# Display_Interfaces.net
KiCad netlist of a schematic drawn in Altium Designer
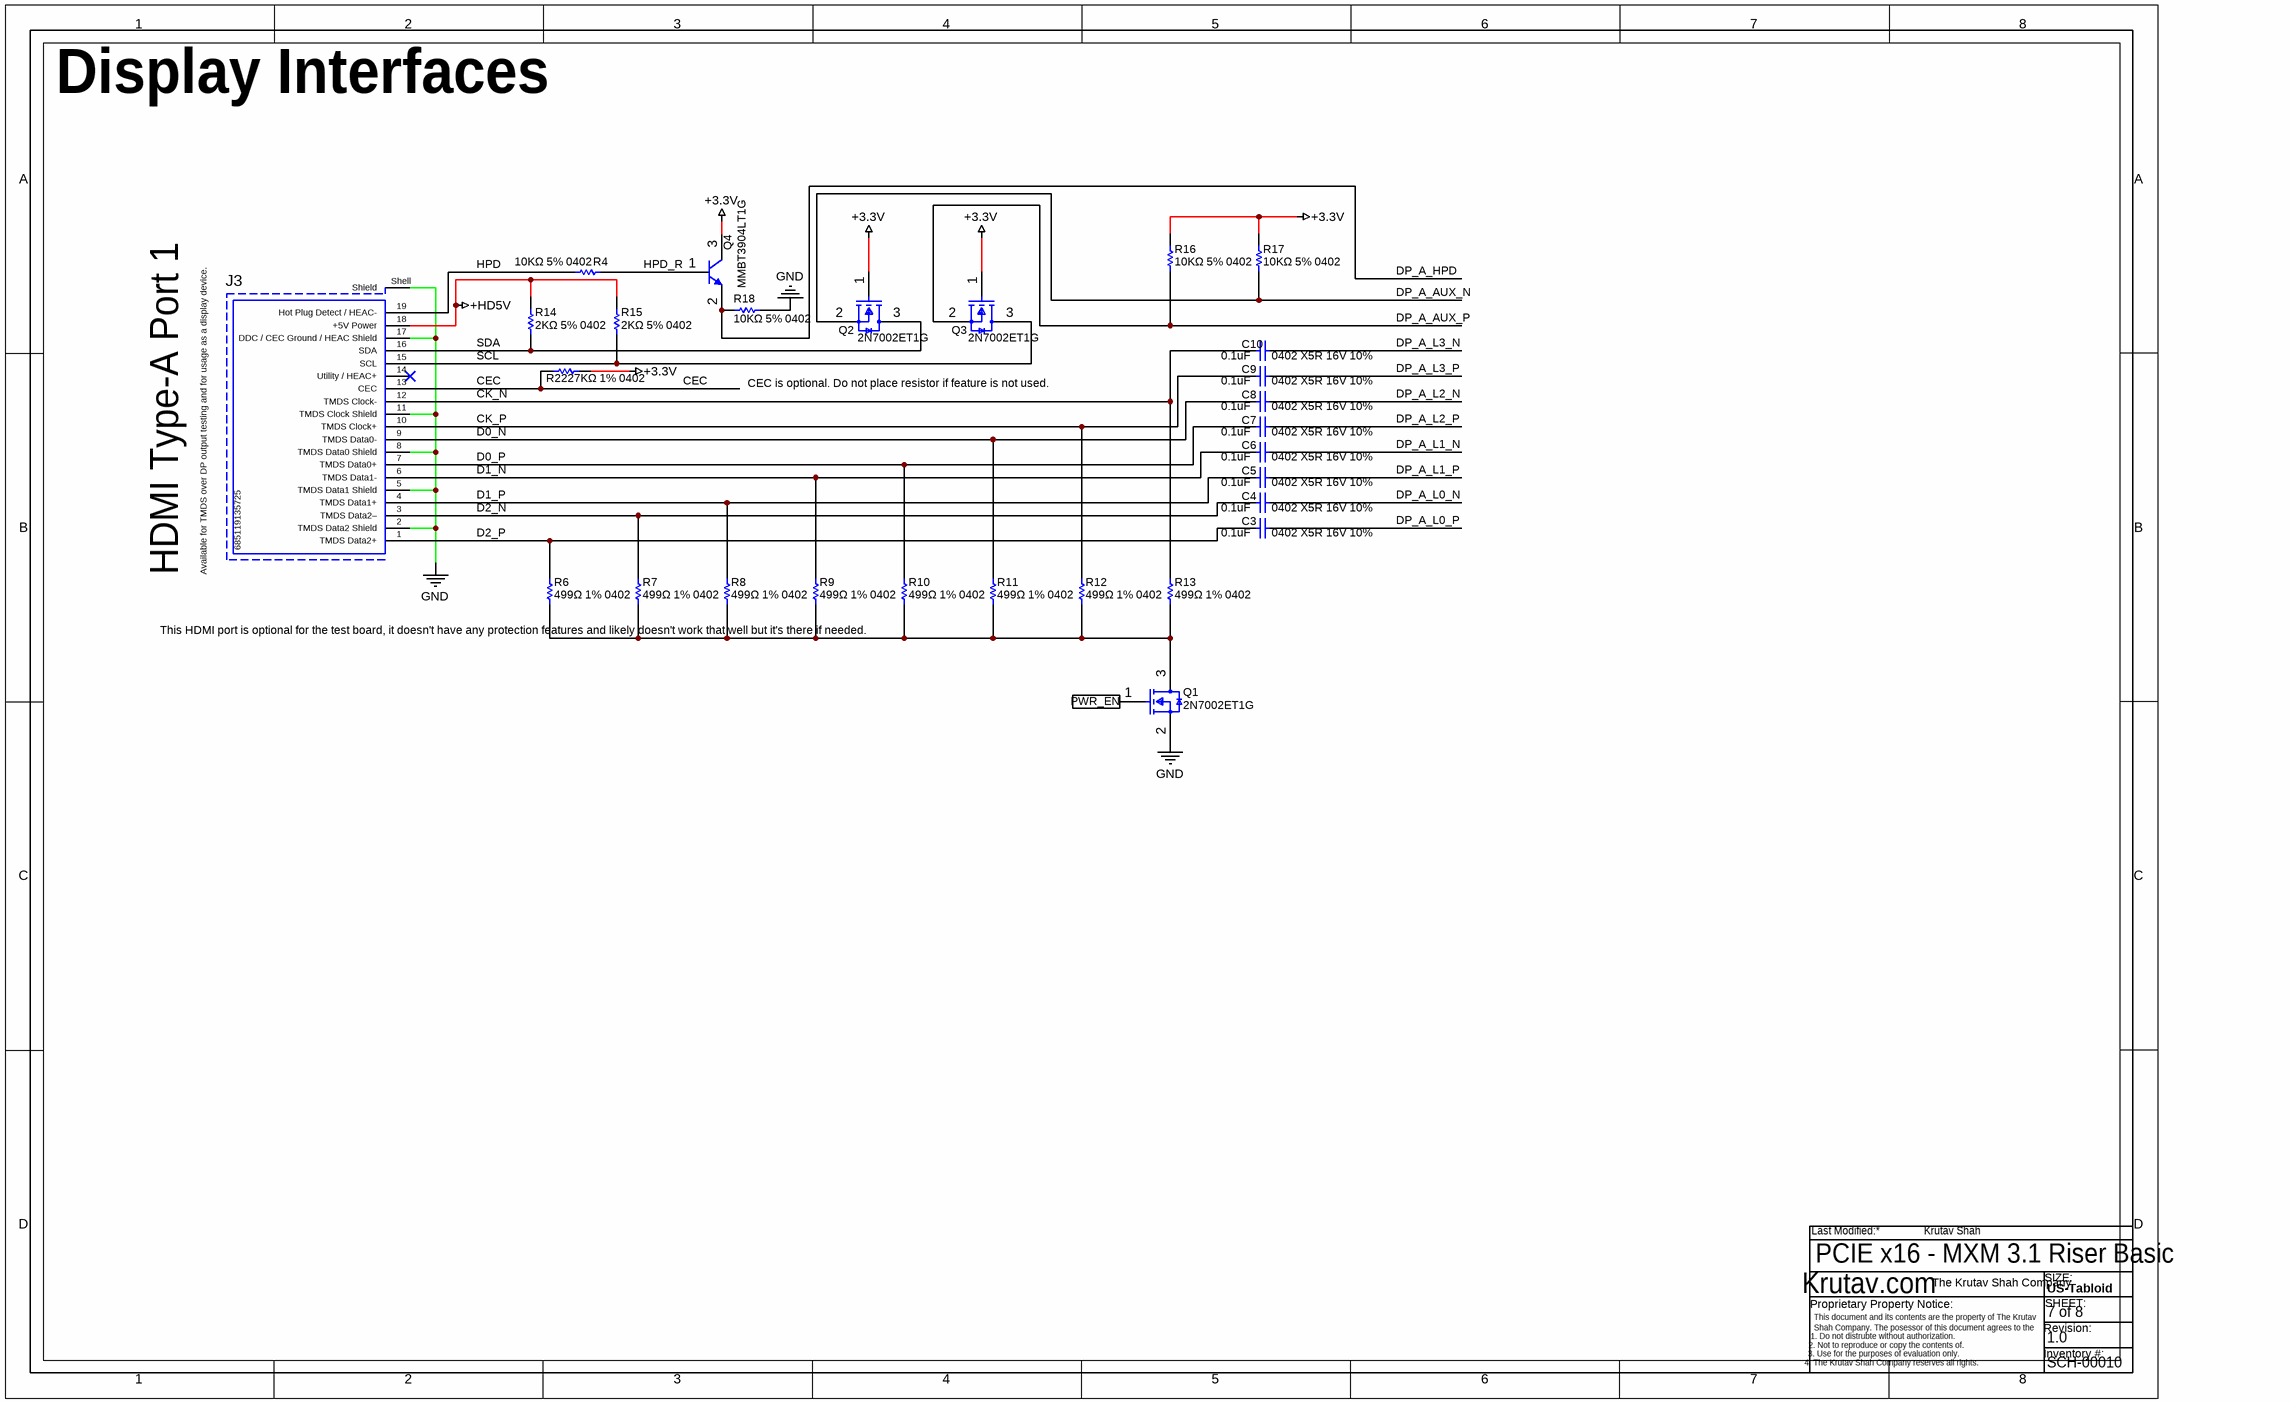
[diagram p0: Display Interfaces.SchDoc]

(export (version "E")
  (design (tool "Eeschema 10.0.6"))
  (components
    (comp (ref "C3")
      (value "0.1uF       0402 X5R 16V 10%")
      (footprint "CAPC0603X33X15NL03T05")
      (fields (field (name "MANUFACTURER") "Samsung") (field (name "PART NUMBER") "CL03A224MQ3NNNC"))
      (libsource (lib "Altium Content Vault") (part "CAP"))
    )
    (comp (ref "C4")
      (value "0.1uF       0402 X5R 16V 10%")
      (footprint "CAPC0603X33X15NL03T05")
      (fields (field (name "MANUFACTURER") "Samsung") (field (name "PART NUMBER") "CL03A224MQ3NNNC"))
      (libsource (lib "Altium Content Vault") (part "CAP"))
    )
    (comp (ref "C5")
      (value "0.1uF       0402 X5R 16V 10%")
      (footprint "CAPC0603X33X15NL03T05")
      (fields (field (name "MANUFACTURER") "Samsung") (field (name "PART NUMBER") "CL03A224MQ3NNNC"))
      (libsource (lib "Altium Content Vault") (part "CAP"))
    )
    (comp (ref "C6")
      (value "0.1uF       0402 X5R 16V 10%")
      (footprint "CAPC0603X33X15NL03T05")
      (fields (field (name "MANUFACTURER") "Samsung") (field (name "PART NUMBER") "CL03A224MQ3NNNC"))
      (libsource (lib "Altium Content Vault") (part "CAP"))
    )
    (comp (ref "C7")
      (value "0.1uF       0402 X5R 16V 10%")
      (footprint "CAPC0603X33X15NL03T05")
      (fields (field (name "MANUFACTURER") "Samsung") (field (name "PART NUMBER") "CL03A224MQ3NNNC"))
      (libsource (lib "Altium Content Vault") (part "CAP"))
    )
    (comp (ref "C8")
      (value "0.1uF       0402 X5R 16V 10%")
      (footprint "CAPC0603X33X15NL03T05")
      (fields (field (name "MANUFACTURER") "Samsung") (field (name "PART NUMBER") "CL03A224MQ3NNNC"))
      (libsource (lib "Altium Content Vault") (part "CAP"))
    )
    (comp (ref "C9")
      (value "0.1uF       0402 X5R 16V 10%")
      (footprint "CAPC0603X33X15NL03T05")
      (fields (field (name "MANUFACTURER") "Samsung") (field (name "PART NUMBER") "CL03A224MQ3NNNC"))
      (libsource (lib "Altium Content Vault") (part "CAP"))
    )
    (comp (ref "C10")
      (value "0.1uF       0402 X5R 16V 10%")
      (footprint "CAPC0603X33X15NL03T05")
      (fields (field (name "MANUFACTURER") "Samsung") (field (name "PART NUMBER") "CL03A224MQ3NNNC"))
      (libsource (lib "Altium Content Vault") (part "CAP"))
    )
    (comp (ref "J3")
      (value "685119135725")
      (footprint "685119135725")
      (description "HDMI Type A Receptacle WR-COM, Horizontal, SMT, with M3 Screw Flange")
      (fields (field (name "MANUFACTURER") "Wurth Elektronik") (field (name "PUBLISHER") "WurthElektronik"))
      (libsource (lib "Altium Content Vault") (part "WE-CN-1P-1F-HD19"))
    )
    (comp (ref "Q1")
      (value "2N7002ET1G")
      (footprint "FP-318-08-IPC_A")
      (description "MOSFET N-CH 60V 260MA SOT-23")
      (libsource (lib "Altium Content Vault") (part "a04dfd38ebfed9f67ad7f4c51a87371"))
    )
    (comp (ref "Q2")
      (value "2N7002ET1G")
      (footprint "FP-318-08-IPC_A")
      (description "MOSFET N-CH 60V 260MA SOT-23")
      (libsource (lib "Altium Content Vault") (part "a04dfd38ebfed9f67ad7f4c51a87371"))
    )
    (comp (ref "Q3")
      (value "2N7002ET1G")
      (footprint "FP-318-08-IPC_A")
      (description "MOSFET N-CH 60V 260MA SOT-23")
      (libsource (lib "Altium Content Vault") (part "a04dfd38ebfed9f67ad7f4c51a87371"))
    )
    (comp (ref "Q4")
      (value "MMBT3904LT1G")
      (footprint "ONSC-SOT-23-3-318-08_V")
      (description "General Purpose Transistor, NPN Silicon, 3-Pin SOT-23, Pb-Free, Tape and Reel")
      (fields (field (name "MANUFACTURER") "On Semiconductor"))
      (libsource (lib "Altium Content Vault") (part "ONSC-NPN-B1E2C3-3"))
    )
    (comp (ref "R4")
      (value "10KΩ 5% 0402")
      (footprint "RESC0201(0603)_L")
      (description "1M 0.05W 1% 0201 (0603 Metric)  SMD")
      (fields (field (name "TOLERANCE") "1 %") (field (name "POWER") "0.05 W"))
      (libsource (lib "Altium Content Vault") (part "RES"))
    )
    (comp (ref "R6")
      (value "499Ω 1% 0402")
      (footprint "RESC0201(0603)_L")
      (description "1M 0.05W 1% 0201 (0603 Metric)  SMD")
      (fields (field (name "TOLERANCE") "1 %") (field (name "POWER") "0.05 W"))
      (libsource (lib "Altium Content Vault") (part "RES"))
    )
    (comp (ref "R7")
      (value "499Ω 1% 0402")
      (footprint "RESC0201(0603)_L")
      (description "1M 0.05W 1% 0201 (0603 Metric)  SMD")
      (fields (field (name "TOLERANCE") "1 %") (field (name "POWER") "0.05 W"))
      (libsource (lib "Altium Content Vault") (part "RES"))
    )
    (comp (ref "R8")
      (value "499Ω 1% 0402")
      (footprint "RESC0201(0603)_L")
      (description "1M 0.05W 1% 0201 (0603 Metric)  SMD")
      (fields (field (name "TOLERANCE") "1 %") (field (name "POWER") "0.05 W"))
      (libsource (lib "Altium Content Vault") (part "RES"))
    )
    (comp (ref "R9")
      (value "499Ω 1% 0402")
      (footprint "RESC0201(0603)_L")
      (description "1M 0.05W 1% 0201 (0603 Metric)  SMD")
      (fields (field (name "TOLERANCE") "1 %") (field (name "POWER") "0.05 W"))
      (libsource (lib "Altium Content Vault") (part "RES"))
    )
    (comp (ref "R10")
      (value "499Ω 1% 0402")
      (footprint "RESC0201(0603)_L")
      (description "1M 0.05W 1% 0201 (0603 Metric)  SMD")
      (fields (field (name "TOLERANCE") "1 %") (field (name "POWER") "0.05 W"))
      (libsource (lib "Altium Content Vault") (part "RES"))
    )
    (comp (ref "R11")
      (value "499Ω 1% 0402")
      (footprint "RESC0201(0603)_L")
      (description "1M 0.05W 1% 0201 (0603 Metric)  SMD")
      (fields (field (name "TOLERANCE") "1 %") (field (name "POWER") "0.05 W"))
      (libsource (lib "Altium Content Vault") (part "RES"))
    )
    (comp (ref "R12")
      (value "499Ω 1% 0402")
      (footprint "RESC0201(0603)_L")
      (description "1M 0.05W 1% 0201 (0603 Metric)  SMD")
      (fields (field (name "TOLERANCE") "1 %") (field (name "POWER") "0.05 W"))
      (libsource (lib "Altium Content Vault") (part "RES"))
    )
    (comp (ref "R13")
      (value "499Ω 1% 0402")
      (footprint "RESC0201(0603)_L")
      (description "1M 0.05W 1% 0201 (0603 Metric)  SMD")
      (fields (field (name "TOLERANCE") "1 %") (field (name "POWER") "0.05 W"))
      (libsource (lib "Altium Content Vault") (part "RES"))
    )
    (comp (ref "R14")
      (value "2KΩ 5% 0402")
      (footprint "RESC0201(0603)_L")
      (description "1M 0.05W 1% 0201 (0603 Metric)  SMD")
      (fields (field (name "TOLERANCE") "1 %") (field (name "POWER") "0.05 W"))
      (libsource (lib "Altium Content Vault") (part "RES"))
    )
    (comp (ref "R15")
      (value "2KΩ 5% 0402")
      (footprint "RESC0201(0603)_L")
      (description "1M 0.05W 1% 0201 (0603 Metric)  SMD")
      (fields (field (name "TOLERANCE") "1 %") (field (name "POWER") "0.05 W"))
      (libsource (lib "Altium Content Vault") (part "RES"))
    )
    (comp (ref "R16")
      (value "10KΩ 5% 0402")
      (footprint "RESC0201(0603)_L")
      (description "1M 0.05W 1% 0201 (0603 Metric)  SMD")
      (fields (field (name "TOLERANCE") "1 %") (field (name "POWER") "0.05 W"))
      (libsource (lib "Altium Content Vault") (part "RES"))
    )
    (comp (ref "R17")
      (value "10KΩ 5% 0402")
      (footprint "RESC0201(0603)_L")
      (description "1M 0.05W 1% 0201 (0603 Metric)  SMD")
      (fields (field (name "TOLERANCE") "1 %") (field (name "POWER") "0.05 W"))
      (libsource (lib "Altium Content Vault") (part "RES"))
    )
    (comp (ref "R18")
      (value "10KΩ 5% 0402")
      (footprint "RESC0201(0603)_L")
      (description "1M 0.05W 1% 0201 (0603 Metric)  SMD")
      (fields (field (name "TOLERANCE") "1 %") (field (name "POWER") "0.05 W"))
      (libsource (lib "Altium Content Vault") (part "RES"))
    )
    (comp (ref "R22")
      (value "27KΩ 1% 0402")
      (footprint "RESC0201(0603)_L")
      (description "1M 0.05W 1% 0201 (0603 Metric)  SMD")
      (fields (field (name "TOLERANCE") "1 %") (field (name "POWER") "0.05 W"))
      (libsource (lib "Altium Content Vault") (part "RES"))
    )
  )
  (nets
    (net (code "1") (name "+3.3V") (class "Default")
      (node (ref "Q2") (pin "1") (pinfunction "Gate_1") (pintype "passive"))
      (node (ref "Q3") (pin "1") (pinfunction "Gate_1") (pintype "passive"))
      (node (ref "Q4") (pin "3") (pinfunction "C_3") (pintype "passive"))
      (node (ref "R16") (pin "1") (pinfunction "1_1") (pintype "passive"))
      (node (ref "R17") (pin "1") (pinfunction "1_1") (pintype "passive"))
      (node (ref "R22") (pin "1") (pinfunction "1_1") (pintype "passive"))
    )
    (net (code "2") (name "+HD5V") (class "Default")
      (node (ref "J3") (pin "18") (pinfunction "+5V_Power_18") (pintype "passive"))
      (node (ref "R14") (pin "1") (pinfunction "1_1") (pintype "passive"))
      (node (ref "R15") (pin "1") (pinfunction "1_1") (pintype "passive"))
    )
    (net (code "3") (name "/CEC") (class "Default")
      (node (ref "J3") (pin "13") (pinfunction "CEC_13") (pintype "passive"))
      (node (ref "R22") (pin "2") (pinfunction "2_2") (pintype "passive"))
    )
    (net (code "4") (name "/CK_N") (class "Default")
      (node (ref "C10") (pin "1") (pinfunction "1_1") (pintype "passive"))
      (node (ref "J3") (pin "12") (pinfunction "TMDS_Clock-_12") (pintype "passive"))
      (node (ref "R13") (pin "1") (pinfunction "1_1") (pintype "passive"))
    )
    (net (code "5") (name "/CK_P") (class "Default")
      (node (ref "C9") (pin "1") (pinfunction "1_1") (pintype "passive"))
      (node (ref "J3") (pin "10") (pinfunction "TMDS_Clock+_10") (pintype "passive"))
      (node (ref "R12") (pin "1") (pinfunction "1_1") (pintype "passive"))
    )
    (net (code "6") (name "/D0_N") (class "Default")
      (node (ref "C8") (pin "1") (pinfunction "1_1") (pintype "passive"))
      (node (ref "J3") (pin "9") (pinfunction "TMDS_Data0-_9") (pintype "passive"))
      (node (ref "R11") (pin "1") (pinfunction "1_1") (pintype "passive"))
    )
    (net (code "7") (name "/D0_P") (class "Default")
      (node (ref "C7") (pin "1") (pinfunction "1_1") (pintype "passive"))
      (node (ref "J3") (pin "7") (pinfunction "TMDS_Data0+_7") (pintype "passive"))
      (node (ref "R10") (pin "1") (pinfunction "1_1") (pintype "passive"))
    )
    (net (code "8") (name "/D1_N") (class "Default")
      (node (ref "C6") (pin "1") (pinfunction "1_1") (pintype "passive"))
      (node (ref "J3") (pin "6") (pinfunction "TMDS_Data1-_6") (pintype "passive"))
      (node (ref "R9") (pin "1") (pinfunction "1_1") (pintype "passive"))
    )
    (net (code "9") (name "/D1_P") (class "Default")
      (node (ref "C5") (pin "1") (pinfunction "1_1") (pintype "passive"))
      (node (ref "J3") (pin "4") (pinfunction "TMDS_Data1+_4") (pintype "passive"))
      (node (ref "R8") (pin "1") (pinfunction "1_1") (pintype "passive"))
    )
    (net (code "10") (name "/D2_N") (class "Default")
      (node (ref "C4") (pin "1") (pinfunction "1_1") (pintype "passive"))
      (node (ref "J3") (pin "3") (pinfunction "TMDS_Data2–_3") (pintype "passive"))
      (node (ref "R7") (pin "1") (pinfunction "1_1") (pintype "passive"))
    )
    (net (code "11") (name "/D2_P") (class "Default")
      (node (ref "C3") (pin "1") (pinfunction "1_1") (pintype "passive"))
      (node (ref "J3") (pin "1") (pinfunction "TMDS_Data2+_1") (pintype "passive"))
      (node (ref "R6") (pin "1") (pinfunction "1_1") (pintype "passive"))
    )
    (net (code "12") (name "/DP_A_AUX_N") (class "Default")
      (node (ref "Q2") (pin "2") (pinfunction "Source_2") (pintype "passive"))
      (node (ref "R17") (pin "2") (pinfunction "2_2") (pintype "passive"))
    )
    (net (code "13") (name "/DP_A_AUX_P") (class "Default")
      (node (ref "Q3") (pin "2") (pinfunction "Source_2") (pintype "passive"))
      (node (ref "R16") (pin "2") (pinfunction "2_2") (pintype "passive"))
    )
    (net (code "14") (name "/DP_A_HPD") (class "Default")
      (node (ref "Q4") (pin "2") (pinfunction "E_2") (pintype "passive"))
      (node (ref "R18") (pin "1") (pinfunction "1_1") (pintype "passive"))
    )
    (net (code "15") (name "/DP_A_L0_N") (class "Default")
      (node (ref "C4") (pin "2") (pinfunction "2_2") (pintype "passive"))
    )
    (net (code "16") (name "/DP_A_L0_P") (class "Default")
      (node (ref "C3") (pin "2") (pinfunction "2_2") (pintype "passive"))
    )
    (net (code "17") (name "/DP_A_L1_N") (class "Default")
      (node (ref "C6") (pin "2") (pinfunction "2_2") (pintype "passive"))
    )
    (net (code "18") (name "/DP_A_L1_P") (class "Default")
      (node (ref "C5") (pin "2") (pinfunction "2_2") (pintype "passive"))
    )
    (net (code "19") (name "/DP_A_L2_N") (class "Default")
      (node (ref "C8") (pin "2") (pinfunction "2_2") (pintype "passive"))
    )
    (net (code "20") (name "/DP_A_L2_P") (class "Default")
      (node (ref "C7") (pin "2") (pinfunction "2_2") (pintype "passive"))
    )
    (net (code "21") (name "/DP_A_L3_N") (class "Default")
      (node (ref "C10") (pin "2") (pinfunction "2_2") (pintype "passive"))
    )
    (net (code "22") (name "/DP_A_L3_P") (class "Default")
      (node (ref "C9") (pin "2") (pinfunction "2_2") (pintype "passive"))
    )
    (net (code "23") (name "/HPD") (class "Default")
      (node (ref "J3") (pin "19") (pinfunction "Hot_Plug_Detect_/_HEAC-_19") (pintype "passive"))
      (node (ref "R4") (pin "2") (pinfunction "2_2") (pintype "passive"))
    )
    (net (code "24") (name "/HPD_R") (class "Default")
      (node (ref "Q4") (pin "1") (pinfunction "B_1") (pintype "passive"))
      (node (ref "R4") (pin "1") (pinfunction "1_1") (pintype "passive"))
    )
    (net (code "25") (name "/PWR_EN") (class "Default")
      (node (ref "Q1") (pin "1") (pinfunction "Gate_1") (pintype "passive"))
    )
    (net (code "26") (name "/SCL") (class "Default")
      (node (ref "J3") (pin "15") (pinfunction "SCL_15") (pintype "passive"))
      (node (ref "Q3") (pin "3") (pinfunction "Drain_3") (pintype "passive"))
      (node (ref "R15") (pin "2") (pinfunction "2_2") (pintype "passive"))
    )
    (net (code "27") (name "/SDA") (class "Default")
      (node (ref "J3") (pin "16") (pinfunction "SDA_16") (pintype "passive"))
      (node (ref "Q2") (pin "3") (pinfunction "Drain_3") (pintype "passive"))
      (node (ref "R14") (pin "2") (pinfunction "2_2") (pintype "passive"))
    )
    (net (code "28") (name "GND") (class "Default")
      (node (ref "J3") (pin "11") (pinfunction "TMDS_Clock_Shield_11") (pintype "passive"))
      (node (ref "J3") (pin "17") (pinfunction "DDC_/_CEC_Ground_/_HEAC_Shield_17") (pintype "passive"))
      (node (ref "J3") (pin "2") (pinfunction "TMDS_Data2_Shield_2") (pintype "passive"))
      (node (ref "J3") (pin "5") (pinfunction "TMDS_Data1_Shield_5") (pintype "passive"))
      (node (ref "J3") (pin "8") (pinfunction "TMDS_Data0_Shield_8") (pintype "passive"))
      (node (ref "J3") (pin "Shell") (pinfunction "Shield_Shell") (pintype "passive"))
      (node (ref "Q1") (pin "2") (pinfunction "Source_2") (pintype "passive"))
      (node (ref "R18") (pin "2") (pinfunction "2_2") (pintype "passive"))
    )
    (net (code "29") (name "Net-(Q1-Drain)") (class "Default")
      (node (ref "Q1") (pin "3") (pinfunction "Drain_3") (pintype "passive"))
      (node (ref "R10") (pin "2") (pinfunction "2_2") (pintype "passive"))
      (node (ref "R11") (pin "2") (pinfunction "2_2") (pintype "passive"))
      (node (ref "R12") (pin "2") (pinfunction "2_2") (pintype "passive"))
      (node (ref "R13") (pin "2") (pinfunction "2_2") (pintype "passive"))
      (node (ref "R6") (pin "2") (pinfunction "2_2") (pintype "passive"))
      (node (ref "R7") (pin "2") (pinfunction "2_2") (pintype "passive"))
      (node (ref "R8") (pin "2") (pinfunction "2_2") (pintype "passive"))
      (node (ref "R9") (pin "2") (pinfunction "2_2") (pintype "passive"))
    )
    (net (code "30") (name "unconnected-(J3-Utility_{slash}_HEAC+-Pad14)") (class "Default")
      (node (ref "J3") (pin "14") (pinfunction "Utility_/_HEAC+_14") (pintype "passive+no_connect"))
    )
  )
)
